# keg-vol-weight-mon.net
KiCad netlist of a schematic drawn in EAGLE
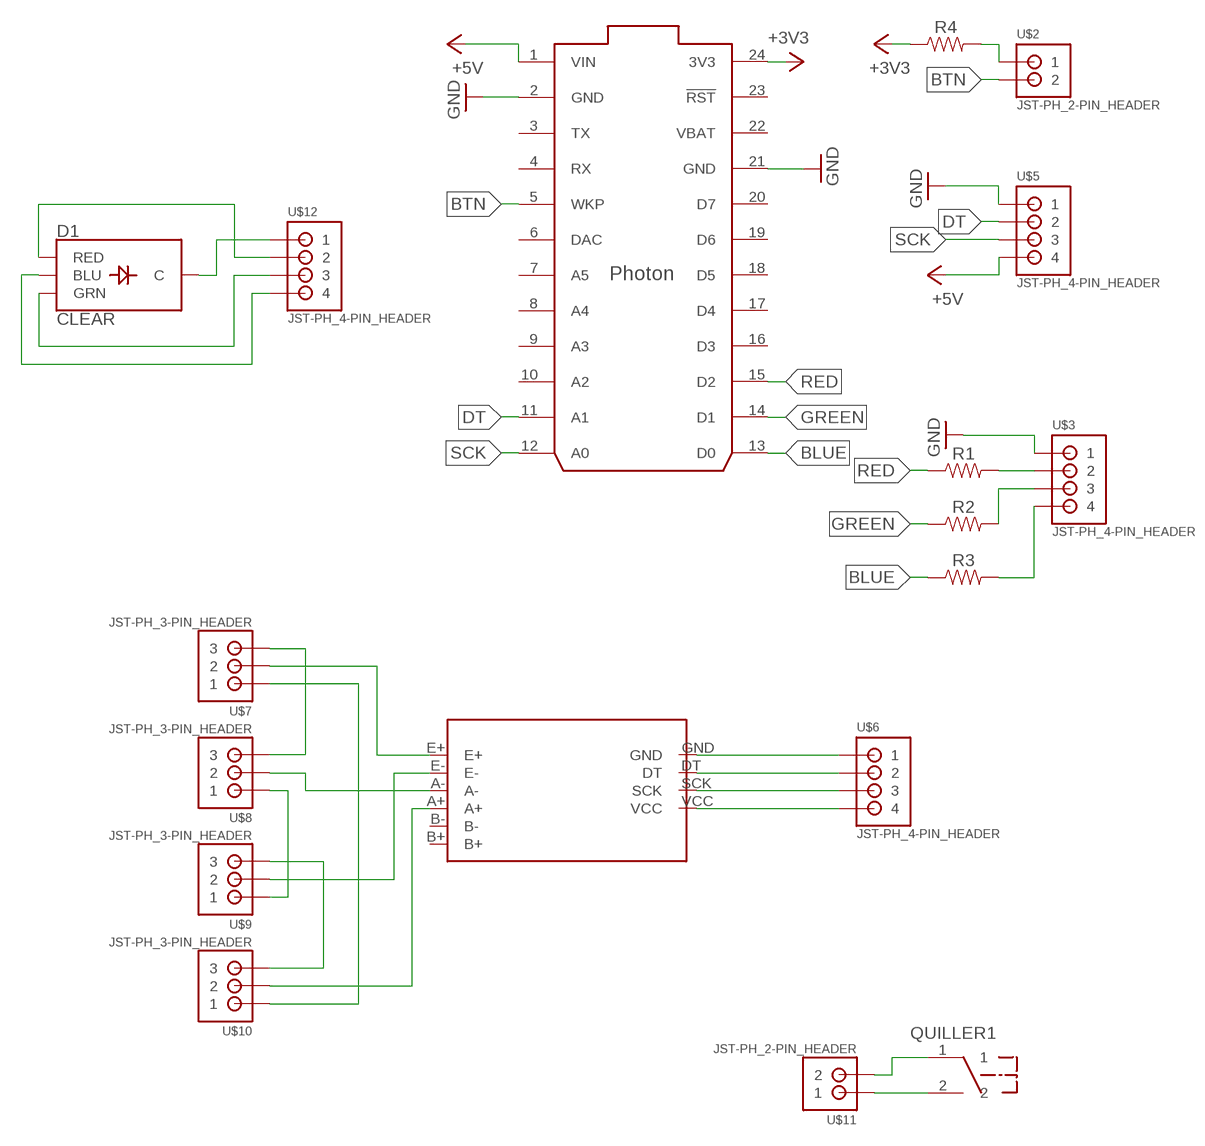
[diagram p0: schematic, sheet 1]

(export (version "E")
  (design (tool "Eeschema 10.0.6"))
  (components
    (comp (ref "D1")
      (value "CLEAR")
      (footprint "eagle-import:LED-RGB-THRU")
      (libsource (lib "eagle-import") (part "LED-RGB-CCCLEAR"))
    )
    (comp (ref "QUILLER1")
      (value "6MM-2PIN-TAC-MOM-SWITCH")
      (footprint "eagle-import:6MM-2PIN-TAC-MOM-SWITCH")
      (libsource (lib "eagle-import") (part "6MM-2PIN-TAC-MOM-SWITCH"))
    )
    (comp (ref "R1")
      (value "RESISTORAXIAL-0.3")
      (footprint "eagle-import:AXIAL-0.3")
      (libsource (lib "eagle-import") (part "RESISTORAXIAL-0.3"))
    )
    (comp (ref "R2")
      (value "RESISTORAXIAL-0.3")
      (footprint "eagle-import:AXIAL-0.3")
      (libsource (lib "eagle-import") (part "RESISTORAXIAL-0.3"))
    )
    (comp (ref "R3")
      (value "RESISTORAXIAL-0.3")
      (footprint "eagle-import:AXIAL-0.3")
      (libsource (lib "eagle-import") (part "RESISTORAXIAL-0.3"))
    )
    (comp (ref "R4")
      (value "RESISTORAXIAL-0.3")
      (footprint "eagle-import:AXIAL-0.3")
      (libsource (lib "eagle-import") (part "RESISTORAXIAL-0.3"))
    )
    (comp (ref "U$1")
      (value "PHOTON_WITH_HEADERS")
      (footprint "eagle-import:PHOTON")
      (libsource (lib "eagle-import") (part "PHOTON_WITH_HEADERS"))
    )
    (comp (ref "U$2")
      (value "JST-PH_2-PIN_HEADER")
      (footprint "eagle-import:JST_B2B-PH_HEADER")
      (libsource (lib "eagle-import") (part "JST-PH_2-PIN_HEADER"))
    )
    (comp (ref "U$3")
      (value "JST-PH_4-PIN_HEADER")
      (footprint "eagle-import:JST_B4B-PH_HEADER")
      (libsource (lib "eagle-import") (part "JST-PH_4-PIN_HEADER"))
    )
    (comp (ref "U$4")
      (value "HX711A")
      (footprint "eagle-import:HX711")
      (libsource (lib "eagle-import") (part "HX711A"))
    )
    (comp (ref "U$5")
      (value "JST-PH_4-PIN_HEADER")
      (footprint "eagle-import:JST_B4B-PH_HEADER")
      (libsource (lib "eagle-import") (part "JST-PH_4-PIN_HEADER"))
    )
    (comp (ref "U$6")
      (value "JST-PH_4-PIN_HEADER")
      (footprint "eagle-import:JST_B4B-PH_HEADER")
      (libsource (lib "eagle-import") (part "JST-PH_4-PIN_HEADER"))
    )
    (comp (ref "U$7")
      (value "JST-PH_3-PIN_HEADER")
      (footprint "eagle-import:JST_B3B-PH_HEADER")
      (libsource (lib "eagle-import") (part "JST-PH_3-PIN_HEADER"))
    )
    (comp (ref "U$8")
      (value "JST-PH_3-PIN_HEADER")
      (footprint "eagle-import:JST_B3B-PH_HEADER")
      (libsource (lib "eagle-import") (part "JST-PH_3-PIN_HEADER"))
    )
    (comp (ref "U$9")
      (value "JST-PH_3-PIN_HEADER")
      (footprint "eagle-import:JST_B3B-PH_HEADER")
      (libsource (lib "eagle-import") (part "JST-PH_3-PIN_HEADER"))
    )
    (comp (ref "U$10")
      (value "JST-PH_3-PIN_HEADER")
      (footprint "eagle-import:JST_B3B-PH_HEADER")
      (libsource (lib "eagle-import") (part "JST-PH_3-PIN_HEADER"))
    )
    (comp (ref "U$11")
      (value "JST-PH_2-PIN_HEADER")
      (footprint "eagle-import:JST_B2B-PH_HEADER")
      (libsource (lib "eagle-import") (part "JST-PH_2-PIN_HEADER"))
    )
    (comp (ref "U$12")
      (value "JST-PH_4-PIN_HEADER")
      (footprint "eagle-import:JST_B4B-PH_HEADER")
      (libsource (lib "eagle-import") (part "JST-PH_4-PIN_HEADER"))
    )
  )
  (nets
    (net (code "1") (name "+3V3") (class "Default")
      (node (ref "R4") (pin "P$1") (pinfunction "1_P$1") (pintype "passive"))
      (node (ref "U$1") (pin "24") (pinfunction "3V3_24") (pintype "power_in"))
    )
    (net (code "2") (name "+5V") (class "Default")
      (node (ref "U$1") (pin "1") (pinfunction "VIN_1") (pintype "power_in"))
      (node (ref "U$5") (pin "P4") (pinfunction "4_P4") (pintype "bidirectional"))
    )
    (net (code "3") (name "/VBAT") (class "Default")
      (node (ref "U$1") (pin "22") (pinfunction "VBAT_22") (pintype "power_in"))
    )
    (net (code "4") (name "BLUE") (class "Default")
      (node (ref "R3") (pin "P$1") (pinfunction "1_P$1") (pintype "passive"))
      (node (ref "U$1") (pin "13") (pinfunction "D0_13") (pintype "bidirectional"))
    )
    (net (code "5") (name "BTN") (class "Default")
      (node (ref "U$1") (pin "5") (pinfunction "WKP_5") (pintype "bidirectional"))
      (node (ref "U$2") (pin "P2") (pinfunction "2_P2") (pintype "bidirectional"))
    )
    (net (code "6") (name "DT") (class "Default")
      (node (ref "U$1") (pin "11") (pinfunction "A1_11") (pintype "bidirectional"))
      (node (ref "U$5") (pin "P2") (pinfunction "2_P2") (pintype "bidirectional"))
    )
    (net (code "7") (name "GND") (class "Default")
      (node (ref "U$1") (pin "2") (pinfunction "GND_2") (pintype "power_in"))
      (node (ref "U$1") (pin "21") (pinfunction "GND_21") (pintype "power_in"))
      (node (ref "U$3") (pin "P1") (pinfunction "1_P1") (pintype "bidirectional"))
      (node (ref "U$5") (pin "P1") (pinfunction "1_P1") (pintype "bidirectional"))
    )
    (net (code "8") (name "GREEN") (class "Default")
      (node (ref "R2") (pin "P$1") (pinfunction "1_P$1") (pintype "passive"))
      (node (ref "U$1") (pin "14") (pinfunction "D1_14") (pintype "bidirectional"))
    )
    (net (code "9") (name "Net-(D1-BLU)") (class "Default")
      (node (ref "D1") (pin "4") (pinfunction "BLU_4") (pintype "bidirectional"))
      (node (ref "U$12") (pin "P4") (pinfunction "4_P4") (pintype "bidirectional"))
    )
    (net (code "10") (name "Net-(D1-C)") (class "Default")
      (node (ref "D1") (pin "2") (pinfunction "C_2") (pintype "bidirectional"))
      (node (ref "U$12") (pin "P1") (pinfunction "1_P1") (pintype "bidirectional"))
    )
    (net (code "11") (name "Net-(D1-GRN)") (class "Default")
      (node (ref "D1") (pin "3") (pinfunction "GRN_3") (pintype "bidirectional"))
      (node (ref "U$12") (pin "P3") (pinfunction "3_P3") (pintype "bidirectional"))
    )
    (net (code "12") (name "Net-(D1-RED)") (class "Default")
      (node (ref "D1") (pin "1") (pinfunction "RED_1") (pintype "bidirectional"))
      (node (ref "U$12") (pin "P2") (pinfunction "2_P2") (pintype "bidirectional"))
    )
    (net (code "13") (name "Net-(R1-2)") (class "Default")
      (node (ref "R1") (pin "P$2") (pinfunction "2_P$2") (pintype "passive"))
      (node (ref "U$3") (pin "P2") (pinfunction "2_P2") (pintype "bidirectional"))
    )
    (net (code "14") (name "Net-(R2-2)") (class "Default")
      (node (ref "R2") (pin "P$2") (pinfunction "2_P$2") (pintype "passive"))
      (node (ref "U$3") (pin "P3") (pinfunction "3_P3") (pintype "bidirectional"))
    )
    (net (code "15") (name "Net-(R3-2)") (class "Default")
      (node (ref "R3") (pin "P$2") (pinfunction "2_P$2") (pintype "passive"))
      (node (ref "U$3") (pin "P4") (pinfunction "4_P4") (pintype "bidirectional"))
    )
    (net (code "16") (name "Net-(R4-2)") (class "Default")
      (node (ref "R4") (pin "P$2") (pinfunction "2_P$2") (pintype "passive"))
      (node (ref "U$2") (pin "P1") (pinfunction "1_P1") (pintype "bidirectional"))
    )
    (net (code "17") (name "Net-(U$6-1)") (class "Default")
      (node (ref "U$4") (pin "GND") (pinfunction "GND_GND") (pintype "bidirectional"))
      (node (ref "U$6") (pin "P1") (pinfunction "1_P1") (pintype "bidirectional"))
    )
    (net (code "18") (name "Net-(U$6-2)") (class "Default")
      (node (ref "U$4") (pin "DT") (pinfunction "DT_DT") (pintype "bidirectional"))
      (node (ref "U$6") (pin "P2") (pinfunction "2_P2") (pintype "bidirectional"))
    )
    (net (code "19") (name "Net-(U$6-3)") (class "Default")
      (node (ref "U$4") (pin "SCK") (pinfunction "SCK_SCK") (pintype "bidirectional"))
      (node (ref "U$6") (pin "P3") (pinfunction "3_P3") (pintype "bidirectional"))
    )
    (net (code "20") (name "Net-(U$6-4)") (class "Default")
      (node (ref "U$4") (pin "VCC") (pinfunction "VCC_VCC") (pintype "bidirectional"))
      (node (ref "U$6") (pin "P4") (pinfunction "4_P4") (pintype "bidirectional"))
    )
    (net (code "21") (name "Net-(U$7-2)") (class "Default")
      (node (ref "U$4") (pin "E+") (pinfunction "E+_E+") (pintype "bidirectional"))
      (node (ref "U$7") (pin "P2") (pinfunction "2_P2") (pintype "bidirectional"))
    )
    (net (code "22") (name "Net-(U$7-3)") (class "Default")
      (node (ref "U$7") (pin "P3") (pinfunction "3_P3") (pintype "bidirectional"))
      (node (ref "U$8") (pin "P3") (pinfunction "3_P3") (pintype "bidirectional"))
    )
    (net (code "23") (name "Net-(U$8-1)") (class "Default")
      (node (ref "U$8") (pin "P1") (pinfunction "1_P1") (pintype "bidirectional"))
      (node (ref "U$9") (pin "P1") (pinfunction "1_P1") (pintype "bidirectional"))
    )
    (net (code "24") (name "Net-(U$8-2)") (class "Default")
      (node (ref "U$4") (pin "A-") (pinfunction "A-_A-") (pintype "bidirectional"))
      (node (ref "U$8") (pin "P2") (pinfunction "2_P2") (pintype "bidirectional"))
    )
    (net (code "25") (name "Net-(U$9-2)") (class "Default")
      (node (ref "U$4") (pin "E-") (pinfunction "E-_E-") (pintype "bidirectional"))
      (node (ref "U$9") (pin "P2") (pinfunction "2_P2") (pintype "bidirectional"))
    )
    (net (code "26") (name "Net-(U$10-1)") (class "Default")
      (node (ref "U$10") (pin "P1") (pinfunction "1_P1") (pintype "bidirectional"))
      (node (ref "U$7") (pin "P1") (pinfunction "1_P1") (pintype "bidirectional"))
    )
    (net (code "27") (name "Net-(U$10-2)") (class "Default")
      (node (ref "U$10") (pin "P2") (pinfunction "2_P2") (pintype "bidirectional"))
      (node (ref "U$4") (pin "A+") (pinfunction "A+_A+") (pintype "bidirectional"))
    )
    (net (code "28") (name "Net-(U$10-3)") (class "Default")
      (node (ref "U$10") (pin "P3") (pinfunction "3_P3") (pintype "bidirectional"))
      (node (ref "U$9") (pin "P3") (pinfunction "3_P3") (pintype "bidirectional"))
    )
    (net (code "29") (name "Net-(U$11-1)") (class "Default")
      (node (ref "QUILLER1") (pin "2") (pinfunction "2_2") (pintype "bidirectional"))
      (node (ref "U$11") (pin "P1") (pinfunction "1_P1") (pintype "bidirectional"))
    )
    (net (code "30") (name "Net-(U$11-2)") (class "Default")
      (node (ref "QUILLER1") (pin "1") (pinfunction "1_1") (pintype "bidirectional"))
      (node (ref "U$11") (pin "P2") (pinfunction "2_P2") (pintype "bidirectional"))
    )
    (net (code "31") (name "RED") (class "Default")
      (node (ref "R1") (pin "P$1") (pinfunction "1_P$1") (pintype "passive"))
      (node (ref "U$1") (pin "15") (pinfunction "D2_15") (pintype "bidirectional"))
    )
    (net (code "32") (name "SCK") (class "Default")
      (node (ref "U$1") (pin "12") (pinfunction "A0_12") (pintype "bidirectional"))
      (node (ref "U$5") (pin "P3") (pinfunction "3_P3") (pintype "bidirectional"))
    )
    (net (code "33") (name "unconnected-(U$1-A2-Pad10)") (class "Default")
      (node (ref "U$1") (pin "10") (pinfunction "A2_10") (pintype "bidirectional"))
    )
    (net (code "34") (name "unconnected-(U$1-A3-Pad9)") (class "Default")
      (node (ref "U$1") (pin "9") (pinfunction "A3_9") (pintype "bidirectional"))
    )
    (net (code "35") (name "unconnected-(U$1-A4-Pad8)") (class "Default")
      (node (ref "U$1") (pin "8") (pinfunction "A4_8") (pintype "bidirectional"))
    )
    (net (code "36") (name "unconnected-(U$1-A5-Pad7)") (class "Default")
      (node (ref "U$1") (pin "7") (pinfunction "A5_7") (pintype "bidirectional"))
    )
    (net (code "37") (name "unconnected-(U$1-D3-Pad16)") (class "Default")
      (node (ref "U$1") (pin "16") (pinfunction "D3_16") (pintype "bidirectional"))
    )
    (net (code "38") (name "unconnected-(U$1-D4-Pad17)") (class "Default")
      (node (ref "U$1") (pin "17") (pinfunction "D4_17") (pintype "bidirectional"))
    )
    (net (code "39") (name "unconnected-(U$1-D5-Pad18)") (class "Default")
      (node (ref "U$1") (pin "18") (pinfunction "D5_18") (pintype "bidirectional"))
    )
    (net (code "40") (name "unconnected-(U$1-D6-Pad19)") (class "Default")
      (node (ref "U$1") (pin "19") (pinfunction "D6_19") (pintype "bidirectional"))
    )
    (net (code "41") (name "unconnected-(U$1-D7-Pad20)") (class "Default")
      (node (ref "U$1") (pin "20") (pinfunction "D7_20") (pintype "bidirectional"))
    )
    (net (code "42") (name "unconnected-(U$1-DAC-Pad6)") (class "Default")
      (node (ref "U$1") (pin "6") (pinfunction "DAC_6") (pintype "bidirectional"))
    )
    (net (code "43") (name "unconnected-(U$1-RX-Pad4)") (class "Default")
      (node (ref "U$1") (pin "4") (pinfunction "RX_4") (pintype "bidirectional"))
    )
    (net (code "44") (name "unconnected-(U$1-TX-Pad3)") (class "Default")
      (node (ref "U$1") (pin "3") (pinfunction "TX_3") (pintype "bidirectional"))
    )
    (net (code "45") (name "unconnected-(U$1-~{RST}-Pad23)") (class "Default")
      (node (ref "U$1") (pin "23") (pinfunction "~{RST}_23") (pintype "bidirectional"))
    )
    (net (code "46") (name "unconnected-(U$4-PadB+)") (class "Default")
      (node (ref "U$4") (pin "B+") (pinfunction "B+_B+") (pintype "bidirectional"))
    )
    (net (code "47") (name "unconnected-(U$4-PadB-)") (class "Default")
      (node (ref "U$4") (pin "B-") (pinfunction "B-_B-") (pintype "bidirectional"))
    )
  )
)
